# driverControlsMezzanine.net
KiCad netlist of a schematic drawn in Altium Designer
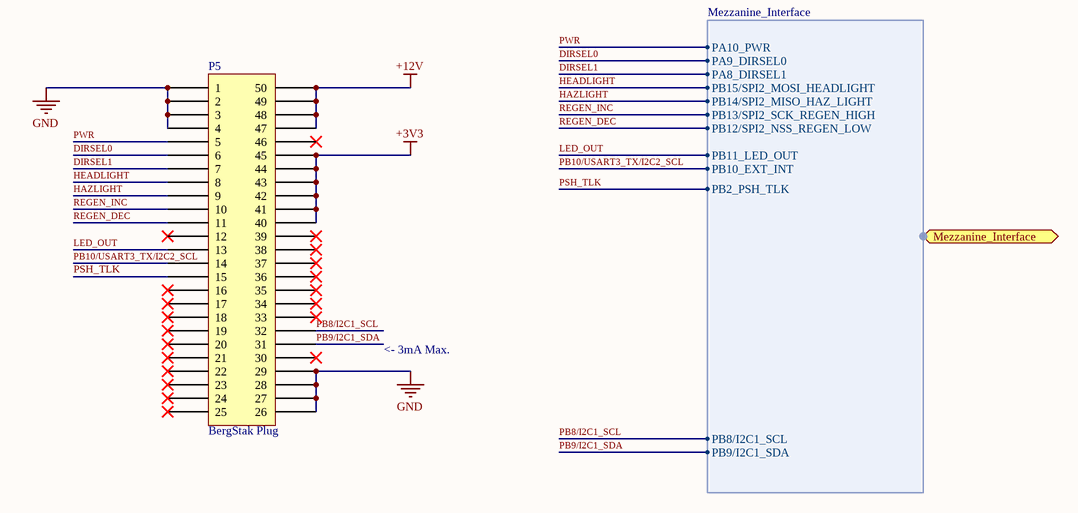
[diagram p0: driverControlsMezzanine.SchDoc]

(export (version "E")
  (design (tool "Eeschema 10.0.6"))
  (components
    (comp (ref "P5")
      (value "BergStak Plug")
      (footprint "CONN, Bergstak 50 Pos Plug")
      (description "50 Position Connector Plug, Outer Shroud Contacts Surface Mount Gold")
      (libsource (lib "Schematic Diagrams") (part "BergStak 50 Position Connector Plug"))
    )
  )
  (nets
    (net (code "2") (name "+3V3") (class "Default")
      (node (ref "P5") (pin "40") (pinfunction "40_40") (pintype "passive"))
      (node (ref "P5") (pin "41") (pinfunction "41_41") (pintype "passive"))
      (node (ref "P5") (pin "42") (pinfunction "42_42") (pintype "passive"))
      (node (ref "P5") (pin "43") (pinfunction "43_43") (pintype "passive"))
      (node (ref "P5") (pin "44") (pinfunction "44_44") (pintype "passive"))
      (node (ref "P5") (pin "45") (pinfunction "45_45") (pintype "passive"))
    )
    (net (code "3") (name "+12V") (class "Default")
      (node (ref "P5") (pin "47") (pinfunction "47_47") (pintype "passive"))
      (node (ref "P5") (pin "48") (pinfunction "48_48") (pintype "passive"))
      (node (ref "P5") (pin "49") (pinfunction "49_49") (pintype "passive"))
      (node (ref "P5") (pin "50") (pinfunction "50_50") (pintype "passive"))
    )
    (net (code "4") (name "/DIRSEL0") (class "Default")
      (node (ref "P5") (pin "6") (pinfunction "6_6") (pintype "passive"))
    )
    (net (code "5") (name "/DIRSEL1") (class "Default")
      (node (ref "P5") (pin "7") (pinfunction "7_7") (pintype "passive"))
    )
    (net (code "6") (name "/HAZLIGHT") (class "Default")
      (node (ref "P5") (pin "9") (pinfunction "9_9") (pintype "passive"))
    )
    (net (code "7") (name "/HEADLIGHT") (class "Default")
      (node (ref "P5") (pin "8") (pinfunction "8_8") (pintype "passive"))
    )
    (net (code "8") (name "/LED_OUT") (class "Default")
      (node (ref "P5") (pin "13") (pinfunction "13_13") (pintype "passive"))
    )
    (net (code "9") (name "/PB8{slash}I2C1_SCL") (class "Default")
      (node (ref "P5") (pin "32") (pinfunction "32_32") (pintype "passive"))
    )
    (net (code "10") (name "/PB9{slash}I2C1_SDA") (class "Default")
      (node (ref "P5") (pin "31") (pinfunction "31_31") (pintype "passive"))
    )
    (net (code "11") (name "/PB10{slash}USART3_TX{slash}I2C2_SCL") (class "Default")
      (node (ref "P5") (pin "14") (pinfunction "14_14") (pintype "passive"))
    )
    (net (code "12") (name "/PSH_TLK") (class "Default")
      (node (ref "P5") (pin "15") (pinfunction "15_15") (pintype "passive"))
    )
    (net (code "13") (name "/PWR") (class "Default")
      (node (ref "P5") (pin "5") (pinfunction "5_5") (pintype "passive"))
    )
    (net (code "14") (name "/REGEN_DEC") (class "Default")
      (node (ref "P5") (pin "11") (pinfunction "11_11") (pintype "passive"))
    )
    (net (code "15") (name "/REGEN_INC") (class "Default")
      (node (ref "P5") (pin "10") (pinfunction "10_10") (pintype "passive"))
    )
    (net (code "17") (name "GND") (class "Default")
      (node (ref "P5") (pin "1") (pinfunction "1_1") (pintype "passive"))
      (node (ref "P5") (pin "2") (pinfunction "2_2") (pintype "passive"))
      (node (ref "P5") (pin "26") (pinfunction "26_26") (pintype "passive"))
      (node (ref "P5") (pin "27") (pinfunction "27_27") (pintype "passive"))
      (node (ref "P5") (pin "28") (pinfunction "28_28") (pintype "passive"))
      (node (ref "P5") (pin "29") (pinfunction "29_29") (pintype "passive"))
      (node (ref "P5") (pin "3") (pinfunction "3_3") (pintype "passive"))
      (node (ref "P5") (pin "4") (pinfunction "4_4") (pintype "passive"))
    )
    (net (code "18") (name "unconnected-(P5-Pad12)") (class "Default")
      (node (ref "P5") (pin "12") (pinfunction "12_12") (pintype "passive+no_connect"))
    )
    (net (code "19") (name "unconnected-(P5-Pad16)") (class "Default")
      (node (ref "P5") (pin "16") (pinfunction "16_16") (pintype "passive+no_connect"))
    )
    (net (code "20") (name "unconnected-(P5-Pad17)") (class "Default")
      (node (ref "P5") (pin "17") (pinfunction "17_17") (pintype "passive+no_connect"))
    )
    (net (code "21") (name "unconnected-(P5-Pad18)") (class "Default")
      (node (ref "P5") (pin "18") (pinfunction "18_18") (pintype "passive+no_connect"))
    )
    (net (code "22") (name "unconnected-(P5-Pad19)") (class "Default")
      (node (ref "P5") (pin "19") (pinfunction "19_19") (pintype "passive+no_connect"))
    )
    (net (code "23") (name "unconnected-(P5-Pad20)") (class "Default")
      (node (ref "P5") (pin "20") (pinfunction "20_20") (pintype "passive+no_connect"))
    )
    (net (code "24") (name "unconnected-(P5-Pad21)") (class "Default")
      (node (ref "P5") (pin "21") (pinfunction "21_21") (pintype "passive+no_connect"))
    )
    (net (code "25") (name "unconnected-(P5-Pad22)") (class "Default")
      (node (ref "P5") (pin "22") (pinfunction "22_22") (pintype "passive+no_connect"))
    )
    (net (code "26") (name "unconnected-(P5-Pad23)") (class "Default")
      (node (ref "P5") (pin "23") (pinfunction "23_23") (pintype "passive+no_connect"))
    )
    (net (code "27") (name "unconnected-(P5-Pad24)") (class "Default")
      (node (ref "P5") (pin "24") (pinfunction "24_24") (pintype "passive+no_connect"))
    )
    (net (code "28") (name "unconnected-(P5-Pad25)") (class "Default")
      (node (ref "P5") (pin "25") (pinfunction "25_25") (pintype "passive+no_connect"))
    )
    (net (code "29") (name "unconnected-(P5-Pad30)") (class "Default")
      (node (ref "P5") (pin "30") (pinfunction "30_30") (pintype "passive+no_connect"))
    )
    (net (code "30") (name "unconnected-(P5-Pad33)") (class "Default")
      (node (ref "P5") (pin "33") (pinfunction "33_33") (pintype "passive+no_connect"))
    )
    (net (code "31") (name "unconnected-(P5-Pad34)") (class "Default")
      (node (ref "P5") (pin "34") (pinfunction "34_34") (pintype "passive+no_connect"))
    )
    (net (code "32") (name "unconnected-(P5-Pad35)") (class "Default")
      (node (ref "P5") (pin "35") (pinfunction "35_35") (pintype "passive+no_connect"))
    )
    (net (code "33") (name "unconnected-(P5-Pad36)") (class "Default")
      (node (ref "P5") (pin "36") (pinfunction "36_36") (pintype "passive+no_connect"))
    )
    (net (code "34") (name "unconnected-(P5-Pad37)") (class "Default")
      (node (ref "P5") (pin "37") (pinfunction "37_37") (pintype "passive+no_connect"))
    )
    (net (code "35") (name "unconnected-(P5-Pad38)") (class "Default")
      (node (ref "P5") (pin "38") (pinfunction "38_38") (pintype "passive+no_connect"))
    )
    (net (code "36") (name "unconnected-(P5-Pad39)") (class "Default")
      (node (ref "P5") (pin "39") (pinfunction "39_39") (pintype "passive+no_connect"))
    )
    (net (code "37") (name "unconnected-(P5-Pad46)") (class "Default")
      (node (ref "P5") (pin "46") (pinfunction "46_46") (pintype "passive+no_connect"))
    )
  )
)
